# SUBBOARD-phase_leg_3p_2L.net
KiCad netlist of a schematic drawn in Altium Designer
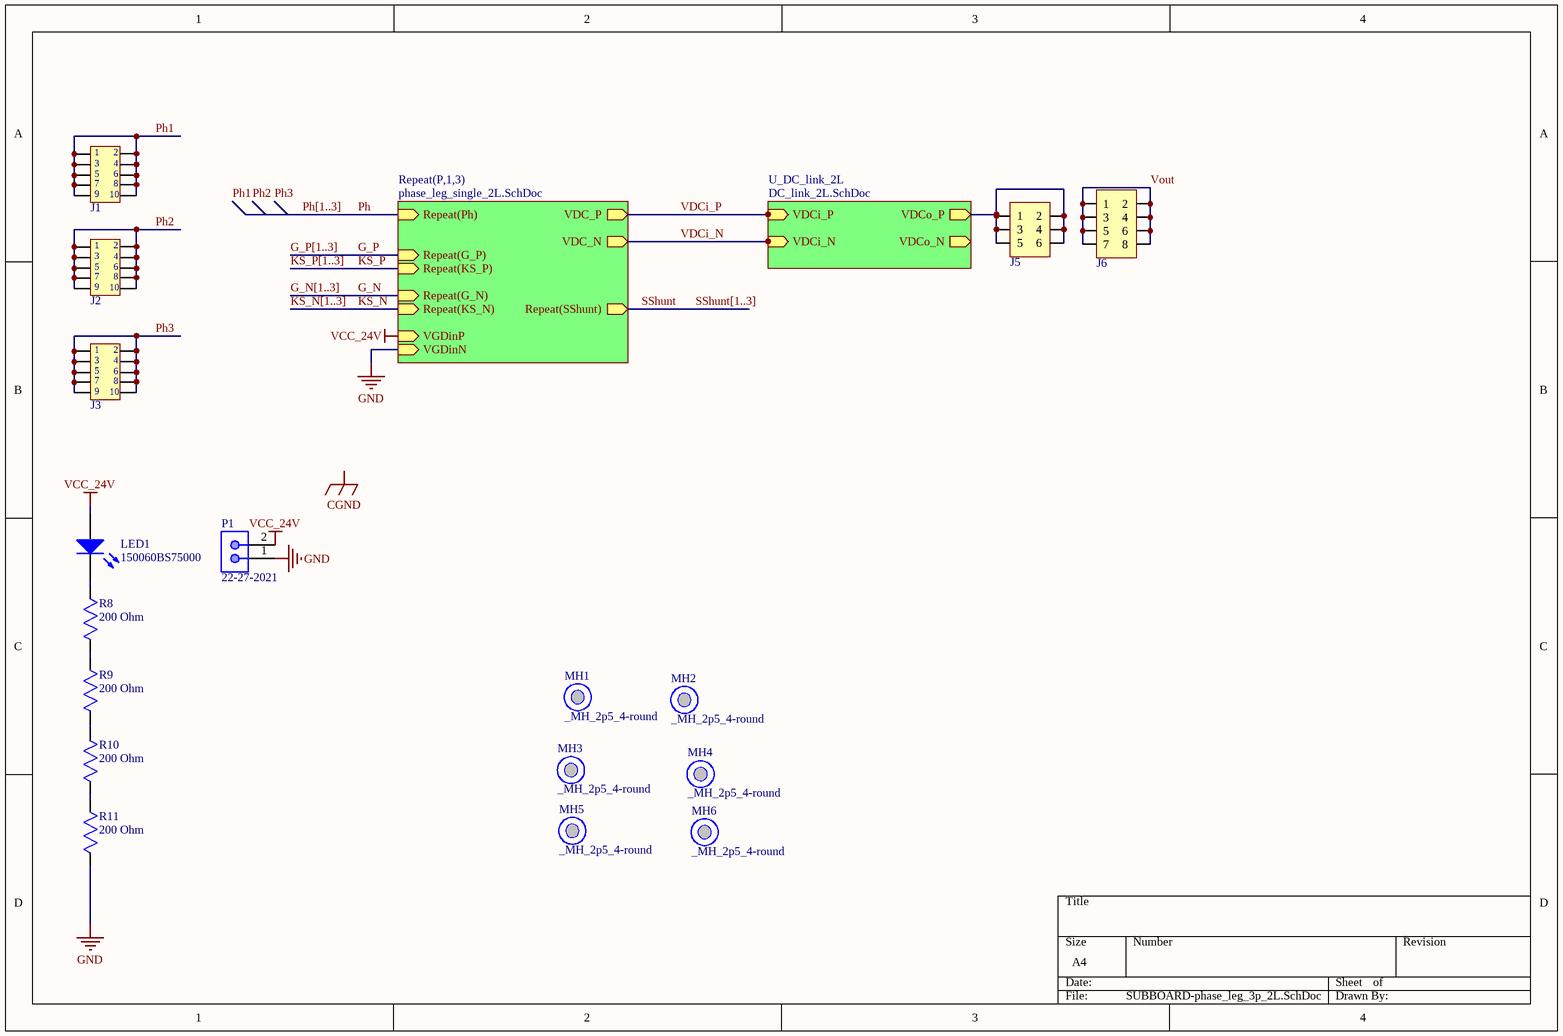
[diagram p0: SUBBOARD-phase_leg_3p_2L.SchDoc]

(export (version "E")
  (design (tool "Eeschema 10.0.6"))
  (components
    (comp (ref "J1")
      (value "IPS1-105-01-L-D-RA")
      (footprint "IPS1-105-01-L-D-RA")
      (fields (field (name "MANUFACTURER") "Samtec"))
      (libsource (lib "Altium_Library_POWERLAB") (part "IPS1-105-01-L-D-RA"))
    )
    (comp (ref "J2")
      (value "IPS1-105-01-L-D-RA")
      (footprint "IPS1-105-01-L-D-RA")
      (fields (field (name "MANUFACTURER") "Samtec"))
      (libsource (lib "Altium_Library_POWERLAB") (part "IPS1-105-01-L-D-RA"))
    )
    (comp (ref "J3")
      (value "IPS1-105-01-L-D-RA")
      (footprint "IPS1-105-01-L-D-RA")
      (fields (field (name "MANUFACTURER") "Samtec"))
      (libsource (lib "Altium_Library_POWERLAB") (part "IPS1-105-01-L-D-RA"))
    )
    (comp (ref "J5")
      (value "SSW-103-01-G-D")
      (footprint "SSW-103-01-G-D")
      (description "Conn Socket Strip SKT 6 POS 2.54mm Solder ST Thru-Hole")
      (fields (field (name "MANUFACTURER") "Samtec"))
      (libsource (lib "Altium_Library_POWERLAB") (part "SSW-103-01-G-D"))
    )
    (comp (ref "J6")
      (value "SSW-104-01-G-D")
      (footprint "SSW-104-01-G-D")
      (description "Conn Socket Strip SKT 8 POS 2.54mm Solder ST Thru-Hole")
      (fields (field (name "MANUFACTURER") "Samtec"))
      (libsource (lib "Altium_Library_POWERLAB") (part "SSW-104-01-G-D"))
    )
    (comp (ref "LED1")
      (value "150060BS75000")
      (footprint "0603_A")
      (description "SMD mono-color Chip LED, WL-SMCW, Blue")
      (fields (field (name "MANUFACTURER") "Wuerth Elektronik"))
      (libsource (lib "Altium Content Vault") (part "WE-LED_K1A2-2"))
    )
    (comp (ref "MH1")
      (value "_MH_2p5_4-round")
      (footprint "_MH_2p5_4-round")
      (description "matching hole 2.5 hole, 4mm pad (round)")
      (libsource (lib "Altium_Library_POWERLAB") (part "_MH_2p5_4-round"))
    )
    (comp (ref "MH2")
      (value "_MH_2p5_4-round")
      (footprint "_MH_2p5_4-round")
      (description "matching hole 2.5 hole, 4mm pad (round)")
      (libsource (lib "Altium_Library_POWERLAB") (part "_MH_2p5_4-round"))
    )
    (comp (ref "MH3")
      (value "_MH_2p5_4-round")
      (footprint "_MH_2p5_4-round")
      (description "matching hole 2.5 hole, 4mm pad (round)")
      (libsource (lib "Altium_Library_POWERLAB") (part "_MH_2p5_4-round"))
    )
    (comp (ref "MH4")
      (value "_MH_2p5_4-round")
      (footprint "_MH_2p5_4-round")
      (description "matching hole 2.5 hole, 4mm pad (round)")
      (libsource (lib "Altium_Library_POWERLAB") (part "_MH_2p5_4-round"))
    )
    (comp (ref "MH5")
      (value "_MH_2p5_4-round")
      (footprint "_MH_2p5_4-round")
      (description "matching hole 2.5 hole, 4mm pad (round)")
      (libsource (lib "Altium_Library_POWERLAB") (part "_MH_2p5_4-round"))
    )
    (comp (ref "MH6")
      (value "_MH_2p5_4-round")
      (footprint "_MH_2p5_4-round")
      (description "matching hole 2.5 hole, 4mm pad (round)")
      (libsource (lib "Altium_Library_POWERLAB") (part "_MH_2p5_4-round"))
    )
    (comp (ref "P1")
      (value "22-27-2021")
      (footprint "MOLX-22-27-2021_V")
      (fields (field (name "MANUFACTURER") "Molex") (field (name "PARTNUMBER") "0022272021"))
      (libsource (lib "Altium Content Vault") (part "CN-1P-M-R2"))
    )
    (comp (ref "R8")
      (value "200 Ohm")
      (footprint "CRCW0603200RFKEAHP")
      (description "CRCW0603200RFKEAHP\r\nRes Thick Film 0603 200 Ohm 1% 0.25W(1/4W) ±100ppm/C Pad SMD Automotive T/R")
      (fields
        (field (name "MANUFACTURER") "Vishay Dale")
        (field (name "MANUFACTURER PART NUMBER") "CRCW0603200RFKEAHP")
      )
      (libsource (lib "Altium_Library_POWERLAB") (part "CRCW0603200RFKEAHP"))
    )
    (comp (ref "R9")
      (value "200 Ohm")
      (footprint "CRCW0603200RFKEAHP")
      (description "CRCW0603200RFKEAHP\r\nRes Thick Film 0603 200 Ohm 1% 0.25W(1/4W) ±100ppm/C Pad SMD Automotive T/R")
      (fields
        (field (name "MANUFACTURER") "Vishay Dale")
        (field (name "MANUFACTURER PART NUMBER") "CRCW0603200RFKEAHP")
      )
      (libsource (lib "Altium_Library_POWERLAB") (part "CRCW0603200RFKEAHP"))
    )
    (comp (ref "R10")
      (value "200 Ohm")
      (footprint "CRCW0603200RFKEAHP")
      (description "CRCW0603200RFKEAHP\r\nRes Thick Film 0603 200 Ohm 1% 0.25W(1/4W) ±100ppm/C Pad SMD Automotive T/R")
      (fields
        (field (name "MANUFACTURER") "Vishay Dale")
        (field (name "MANUFACTURER PART NUMBER") "CRCW0603200RFKEAHP")
      )
      (libsource (lib "Altium_Library_POWERLAB") (part "CRCW0603200RFKEAHP"))
    )
    (comp (ref "R11")
      (value "200 Ohm")
      (footprint "CRCW0603200RFKEAHP")
      (description "CRCW0603200RFKEAHP\r\nRes Thick Film 0603 200 Ohm 1% 0.25W(1/4W) ±100ppm/C Pad SMD Automotive T/R")
      (fields
        (field (name "MANUFACTURER") "Vishay Dale")
        (field (name "MANUFACTURER PART NUMBER") "CRCW0603200RFKEAHP")
      )
      (libsource (lib "Altium_Library_POWERLAB") (part "CRCW0603200RFKEAHP"))
    )
  )
  (nets
    (net (code "25") (name "/Ph1") (class "Default")
      (node (ref "J1") (pin "1") (pinfunction "1_1") (pintype "passive"))
      (node (ref "J1") (pin "10") (pinfunction "10_10") (pintype "passive"))
      (node (ref "J1") (pin "2") (pinfunction "2_2") (pintype "passive"))
      (node (ref "J1") (pin "3") (pinfunction "3_3") (pintype "passive"))
      (node (ref "J1") (pin "4") (pinfunction "4_4") (pintype "passive"))
      (node (ref "J1") (pin "5") (pinfunction "5_5") (pintype "passive"))
      (node (ref "J1") (pin "6") (pinfunction "6_6") (pintype "passive"))
      (node (ref "J1") (pin "7") (pinfunction "7_7") (pintype "passive"))
      (node (ref "J1") (pin "8") (pinfunction "8_8") (pintype "passive"))
      (node (ref "J1") (pin "9") (pinfunction "9_9") (pintype "passive"))
    )
    (net (code "26") (name "/Ph2") (class "Default")
      (node (ref "J2") (pin "1") (pinfunction "1_1") (pintype "passive"))
      (node (ref "J2") (pin "10") (pinfunction "10_10") (pintype "passive"))
      (node (ref "J2") (pin "2") (pinfunction "2_2") (pintype "passive"))
      (node (ref "J2") (pin "3") (pinfunction "3_3") (pintype "passive"))
      (node (ref "J2") (pin "4") (pinfunction "4_4") (pintype "passive"))
      (node (ref "J2") (pin "5") (pinfunction "5_5") (pintype "passive"))
      (node (ref "J2") (pin "6") (pinfunction "6_6") (pintype "passive"))
      (node (ref "J2") (pin "7") (pinfunction "7_7") (pintype "passive"))
      (node (ref "J2") (pin "8") (pinfunction "8_8") (pintype "passive"))
      (node (ref "J2") (pin "9") (pinfunction "9_9") (pintype "passive"))
    )
    (net (code "27") (name "/Ph3") (class "Default")
      (node (ref "J3") (pin "1") (pinfunction "1_1") (pintype "passive"))
      (node (ref "J3") (pin "10") (pinfunction "10_10") (pintype "passive"))
      (node (ref "J3") (pin "2") (pinfunction "2_2") (pintype "passive"))
      (node (ref "J3") (pin "3") (pinfunction "3_3") (pintype "passive"))
      (node (ref "J3") (pin "4") (pinfunction "4_4") (pintype "passive"))
      (node (ref "J3") (pin "5") (pinfunction "5_5") (pintype "passive"))
      (node (ref "J3") (pin "6") (pinfunction "6_6") (pintype "passive"))
      (node (ref "J3") (pin "7") (pinfunction "7_7") (pintype "passive"))
      (node (ref "J3") (pin "8") (pinfunction "8_8") (pintype "passive"))
      (node (ref "J3") (pin "9") (pinfunction "9_9") (pintype "passive"))
    )
    (net (code "34") (name "/VDCo_P") (class "Default")
      (node (ref "J5") (pin "1") (pinfunction "1_1") (pintype "passive"))
      (node (ref "J5") (pin "2") (pinfunction "2_2") (pintype "passive"))
      (node (ref "J5") (pin "3") (pinfunction "3_3") (pintype "passive"))
      (node (ref "J5") (pin "4") (pinfunction "4_4") (pintype "passive"))
      (node (ref "J5") (pin "5") (pinfunction "5_5") (pintype "passive"))
      (node (ref "J5") (pin "6") (pinfunction "6_6") (pintype "passive"))
    )
    (net (code "35") (name "/Vout") (class "Default")
      (node (ref "J6") (pin "1") (pinfunction "1_1") (pintype "passive"))
      (node (ref "J6") (pin "2") (pinfunction "2_2") (pintype "passive"))
      (node (ref "J6") (pin "3") (pinfunction "3_3") (pintype "passive"))
      (node (ref "J6") (pin "4") (pinfunction "4_4") (pintype "passive"))
      (node (ref "J6") (pin "5") (pinfunction "5_5") (pintype "passive"))
      (node (ref "J6") (pin "6") (pinfunction "6_6") (pintype "passive"))
      (node (ref "J6") (pin "7") (pinfunction "7_7") (pintype "passive"))
      (node (ref "J6") (pin "8") (pinfunction "8_8") (pintype "passive"))
    )
    (net (code "37") (name "GND") (class "Default")
      (node (ref "P1") (pin "1") (pinfunction "1_1") (pintype "passive"))
      (node (ref "R11") (pin "2") (pinfunction "2_2") (pintype "passive"))
    )
    (net (code "38") (name "Net-(LED1-K)") (class "Default")
      (node (ref "LED1") (pin "1") (pinfunction "K_1") (pintype "passive"))
      (node (ref "R8") (pin "1") (pinfunction "1_1") (pintype "passive"))
    )
    (net (code "39") (name "Net-(R8-Pad2)") (class "Default")
      (node (ref "R8") (pin "2") (pinfunction "2_2") (pintype "passive"))
      (node (ref "R9") (pin "1") (pinfunction "1_1") (pintype "passive"))
    )
    (net (code "40") (name "Net-(R10-Pad1)") (class "Default")
      (node (ref "R10") (pin "1") (pinfunction "1_1") (pintype "passive"))
      (node (ref "R9") (pin "2") (pinfunction "2_2") (pintype "passive"))
    )
    (net (code "41") (name "Net-(R10-Pad2)") (class "Default")
      (node (ref "R10") (pin "2") (pinfunction "2_2") (pintype "passive"))
      (node (ref "R11") (pin "1") (pinfunction "1_1") (pintype "passive"))
    )
    (net (code "42") (name "VCC_24V") (class "Default")
      (node (ref "LED1") (pin "2") (pinfunction "A_2") (pintype "passive"))
      (node (ref "P1") (pin "2") (pinfunction "2_2") (pintype "passive"))
    )
  )
)
